# circuit_etudiant_2025.net
KiCad netlist of a schematic drawn in Altium Designer
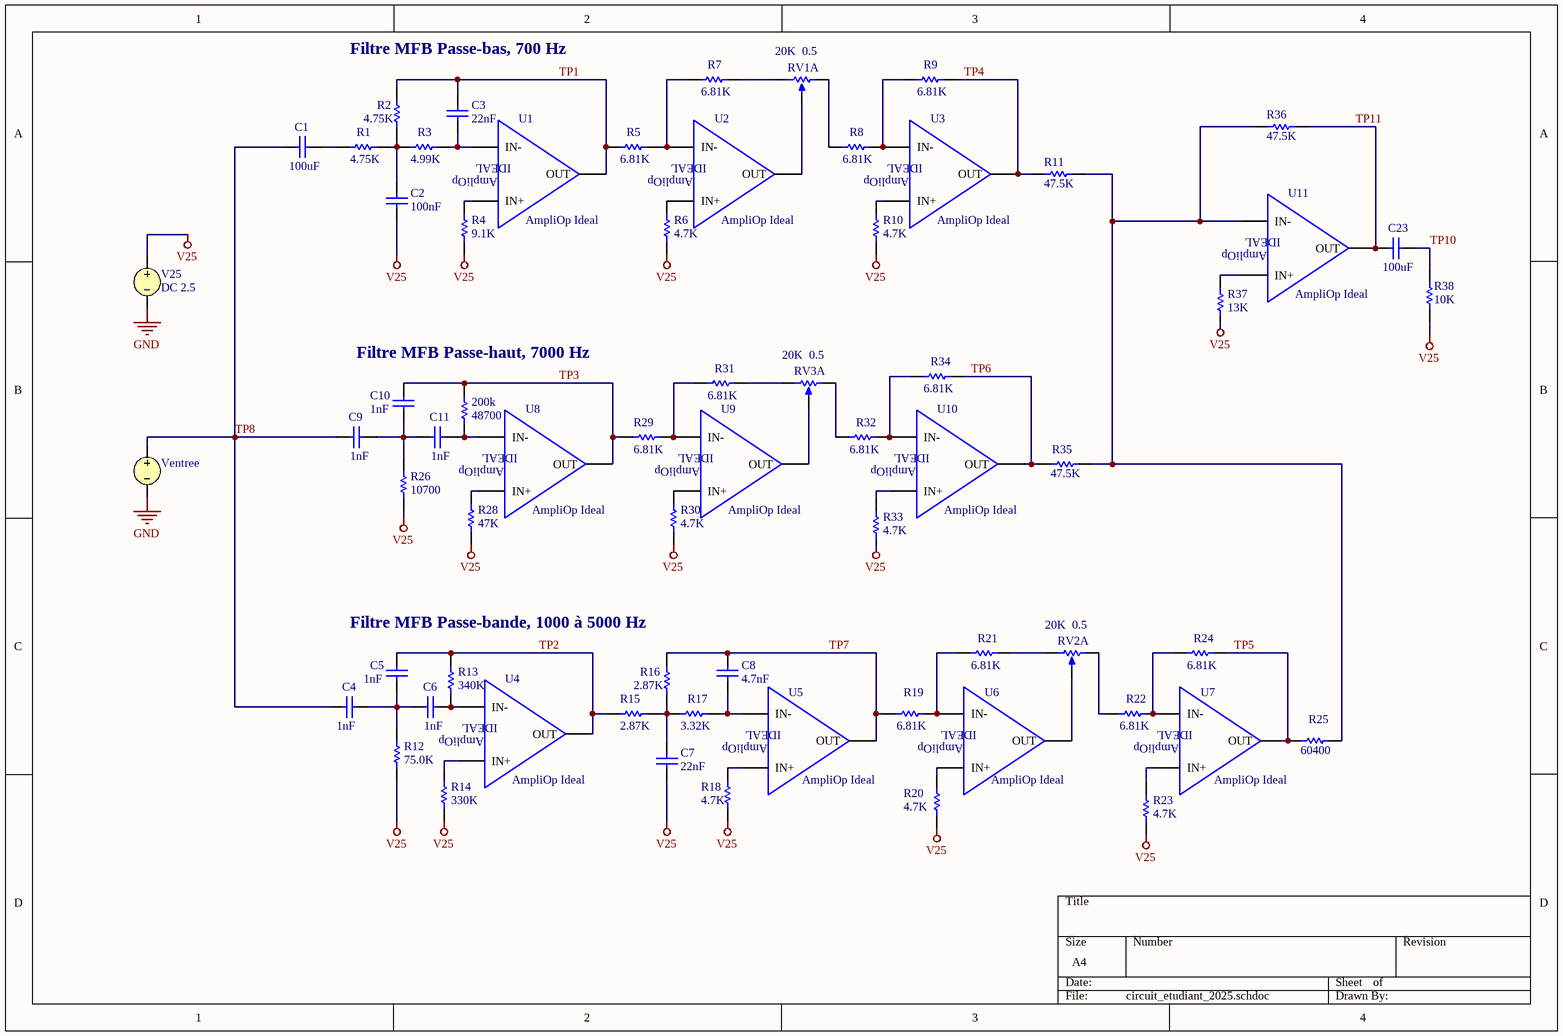
[diagram p0: circuit_etudiant_2025.schdoc]

(export (version "E")
  (design (tool "Eeschema 10.0.6"))
  (components
    (comp (ref "200k")
      (value "48700")
      (footprint "AXIAL-0.3")
      (description "Resistor")
      (fields (field (name "Comment") "Res1") (field (name "PUBLISHER") "Altium Limited"))
      (libsource (lib "Miscellaneous Devices") (part "Res1"))
    )
    (comp (ref "C1")
      (value "100uF")
      (footprint "RAD-0.3")
      (description "Capacitor")
      (fields (field (name "Comment") "Cap") (field (name "PUBLISHER") "Altium Limited"))
      (libsource (lib "Miscellaneous Devices") (part "Cap"))
    )
    (comp (ref "C2")
      (value "100nF")
      (footprint "RAD-0.3")
      (description "Capacitor")
      (fields (field (name "Comment") "Cap") (field (name "PUBLISHER") "Altium Limited"))
      (libsource (lib "Miscellaneous Devices") (part "Cap"))
    )
    (comp (ref "C3")
      (value "22nF")
      (footprint "RAD-0.3")
      (description "Capacitor")
      (fields (field (name "Comment") "Cap") (field (name "PUBLISHER") "Altium Limited"))
      (libsource (lib "Miscellaneous Devices") (part "Cap"))
    )
    (comp (ref "C4")
      (value "1nF")
      (footprint "RAD-0.3")
      (description "Capacitor")
      (fields (field (name "Comment") "Cap") (field (name "PUBLISHER") "Altium Limited"))
      (libsource (lib "Miscellaneous Devices") (part "Cap"))
    )
    (comp (ref "C5")
      (value "1nF")
      (footprint "RAD-0.3")
      (description "Capacitor")
      (fields (field (name "Comment") "Cap") (field (name "PUBLISHER") "Altium Limited"))
      (libsource (lib "Miscellaneous Devices") (part "Cap"))
    )
    (comp (ref "C6")
      (value "1nF")
      (footprint "RAD-0.3")
      (description "Capacitor")
      (fields (field (name "Comment") "Cap") (field (name "PUBLISHER") "Altium Limited"))
      (libsource (lib "Miscellaneous Devices") (part "Cap"))
    )
    (comp (ref "C7")
      (value "22nF")
      (footprint "RAD-0.3")
      (description "Capacitor")
      (fields (field (name "Comment") "Cap") (field (name "PUBLISHER") "Altium Limited"))
      (libsource (lib "Miscellaneous Devices") (part "Cap"))
    )
    (comp (ref "C8")
      (value "4.7nF")
      (footprint "RAD-0.3")
      (description "Capacitor")
      (fields (field (name "Comment") "Cap") (field (name "PUBLISHER") "Altium Limited"))
      (libsource (lib "Miscellaneous Devices") (part "Cap"))
    )
    (comp (ref "C9")
      (value "1nF")
      (footprint "RAD-0.3")
      (description "Capacitor")
      (fields (field (name "Comment") "Cap") (field (name "PUBLISHER") "Altium Limited"))
      (libsource (lib "Miscellaneous Devices") (part "Cap"))
    )
    (comp (ref "C10")
      (value "1nF")
      (footprint "RAD-0.3")
      (description "Capacitor")
      (fields (field (name "Comment") "Cap") (field (name "PUBLISHER") "Altium Limited"))
      (libsource (lib "Miscellaneous Devices") (part "Cap"))
    )
    (comp (ref "C11")
      (value "1nF")
      (footprint "RAD-0.3")
      (description "Capacitor")
      (fields (field (name "Comment") "Cap") (field (name "PUBLISHER") "Altium Limited"))
      (libsource (lib "Miscellaneous Devices") (part "Cap"))
    )
    (comp (ref "C23")
      (value "100uF")
      (footprint "RAD-0.3")
      (description "Capacitor")
      (fields (field (name "Comment") "Cap") (field (name "PUBLISHER") "Altium Limited"))
      (libsource (lib "Miscellaneous Devices") (part "Cap"))
    )
    (comp (ref "R1")
      (value "4.75K")
      (footprint "AXIAL-0.3")
      (description "Resistor")
      (fields (field (name "Comment") "Res1") (field (name "PUBLISHER") "Altium Limited"))
      (libsource (lib "Miscellaneous Devices") (part "Res1"))
    )
    (comp (ref "R2")
      (value "4.75K")
      (footprint "AXIAL-0.3")
      (description "Resistor")
      (fields (field (name "Comment") "Res1") (field (name "PUBLISHER") "Altium Limited"))
      (libsource (lib "Miscellaneous Devices") (part "Res1"))
    )
    (comp (ref "R3")
      (value "4.99K")
      (footprint "AXIAL-0.3")
      (description "Resistor")
      (fields (field (name "Comment") "Res1") (field (name "PUBLISHER") "Altium Limited"))
      (libsource (lib "Miscellaneous Devices") (part "Res1"))
    )
    (comp (ref "R4")
      (value "9.1K")
      (footprint "AXIAL-0.3")
      (description "Resistor")
      (fields (field (name "Comment") "Res1") (field (name "PUBLISHER") "Altium Limited"))
      (libsource (lib "Miscellaneous Devices") (part "Res1"))
    )
    (comp (ref "R5")
      (value "6.81K")
      (footprint "AXIAL-0.3")
      (description "Resistor")
      (fields (field (name "Comment") "Res1") (field (name "PUBLISHER") "Altium Limited"))
      (libsource (lib "Miscellaneous Devices") (part "Res1"))
    )
    (comp (ref "R6")
      (value "4.7K")
      (footprint "AXIAL-0.3")
      (description "Resistor")
      (fields (field (name "Comment") "Res1") (field (name "PUBLISHER") "Altium Limited"))
      (libsource (lib "Miscellaneous Devices") (part "Res1"))
    )
    (comp (ref "R7")
      (value "6.81K")
      (footprint "AXIAL-0.3")
      (description "Resistor")
      (fields (field (name "Comment") "Res1") (field (name "PUBLISHER") "Altium Limited"))
      (libsource (lib "Miscellaneous Devices") (part "Res1"))
    )
    (comp (ref "R8")
      (value "6.81K")
      (footprint "AXIAL-0.3")
      (description "Resistor")
      (fields (field (name "Comment") "Res1") (field (name "PUBLISHER") "Altium Limited"))
      (libsource (lib "Miscellaneous Devices") (part "Res1"))
    )
    (comp (ref "R9")
      (value "6.81K")
      (footprint "AXIAL-0.3")
      (description "Resistor")
      (fields (field (name "Comment") "Res1") (field (name "PUBLISHER") "Altium Limited"))
      (libsource (lib "Miscellaneous Devices") (part "Res1"))
    )
    (comp (ref "R10")
      (value "4.7K")
      (footprint "AXIAL-0.3")
      (description "Resistor")
      (fields (field (name "Comment") "Res1") (field (name "PUBLISHER") "Altium Limited"))
      (libsource (lib "Miscellaneous Devices") (part "Res1"))
    )
    (comp (ref "R11")
      (value "47.5K")
      (footprint "AXIAL-0.3")
      (description "Resistor")
      (fields (field (name "Comment") "Res1") (field (name "PUBLISHER") "Altium Limited"))
      (libsource (lib "Miscellaneous Devices") (part "Res1"))
    )
    (comp (ref "R12")
      (value "75.0K")
      (footprint "AXIAL-0.3")
      (description "Resistor")
      (fields (field (name "Comment") "Res1") (field (name "PUBLISHER") "Altium Limited"))
      (libsource (lib "Miscellaneous Devices") (part "Res1"))
    )
    (comp (ref "R13")
      (value "340K")
      (footprint "AXIAL-0.3")
      (description "Resistor")
      (fields (field (name "Comment") "Res1") (field (name "PUBLISHER") "Altium Limited"))
      (libsource (lib "Miscellaneous Devices") (part "Res1"))
    )
    (comp (ref "R14")
      (value "330K")
      (footprint "AXIAL-0.3")
      (description "Resistor")
      (fields (field (name "Comment") "Res1") (field (name "PUBLISHER") "Altium Limited"))
      (libsource (lib "Miscellaneous Devices") (part "Res1"))
    )
    (comp (ref "R15")
      (value "2.87K")
      (footprint "AXIAL-0.3")
      (description "Resistor")
      (fields (field (name "Comment") "Res1") (field (name "PUBLISHER") "Altium Limited"))
      (libsource (lib "Miscellaneous Devices") (part "Res1"))
    )
    (comp (ref "R16")
      (value "2.87K")
      (footprint "AXIAL-0.3")
      (description "Resistor")
      (fields (field (name "Comment") "Res1") (field (name "PUBLISHER") "Altium Limited"))
      (libsource (lib "Miscellaneous Devices") (part "Res1"))
    )
    (comp (ref "R17")
      (value "3.32K")
      (footprint "AXIAL-0.3")
      (description "Resistor")
      (fields (field (name "Comment") "Res1") (field (name "PUBLISHER") "Altium Limited"))
      (libsource (lib "Miscellaneous Devices") (part "Res1"))
    )
    (comp (ref "R18")
      (value "4.7K")
      (footprint "AXIAL-0.3")
      (description "Resistor")
      (fields (field (name "Comment") "Res1") (field (name "PUBLISHER") "Altium Limited"))
      (libsource (lib "Miscellaneous Devices") (part "Res1"))
    )
    (comp (ref "R19")
      (value "6.81K")
      (footprint "AXIAL-0.3")
      (description "Resistor")
      (fields (field (name "Comment") "Res1") (field (name "PUBLISHER") "Altium Limited"))
      (libsource (lib "Miscellaneous Devices") (part "Res1"))
    )
    (comp (ref "R20")
      (value "4.7K")
      (footprint "AXIAL-0.3")
      (description "Resistor")
      (fields (field (name "Comment") "Res1") (field (name "PUBLISHER") "Altium Limited"))
      (libsource (lib "Miscellaneous Devices") (part "Res1"))
    )
    (comp (ref "R21")
      (value "6.81K")
      (footprint "AXIAL-0.3")
      (description "Resistor")
      (fields (field (name "Comment") "Res1") (field (name "PUBLISHER") "Altium Limited"))
      (libsource (lib "Miscellaneous Devices") (part "Res1"))
    )
    (comp (ref "R22")
      (value "6.81K")
      (footprint "AXIAL-0.3")
      (description "Resistor")
      (fields (field (name "Comment") "Res1") (field (name "PUBLISHER") "Altium Limited"))
      (libsource (lib "Miscellaneous Devices") (part "Res1"))
    )
    (comp (ref "R23")
      (value "4.7K")
      (footprint "AXIAL-0.3")
      (description "Resistor")
      (fields (field (name "Comment") "Res1") (field (name "PUBLISHER") "Altium Limited"))
      (libsource (lib "Miscellaneous Devices") (part "Res1"))
    )
    (comp (ref "R24")
      (value "6.81K")
      (footprint "AXIAL-0.3")
      (description "Resistor")
      (fields (field (name "Comment") "Res1") (field (name "PUBLISHER") "Altium Limited"))
      (libsource (lib "Miscellaneous Devices") (part "Res1"))
    )
    (comp (ref "R25")
      (value "60400")
      (footprint "AXIAL-0.3")
      (description "Resistor")
      (fields (field (name "Comment") "Res1") (field (name "PUBLISHER") "Altium Limited"))
      (libsource (lib "Miscellaneous Devices") (part "Res1"))
    )
    (comp (ref "R26")
      (value "10700")
      (footprint "AXIAL-0.3")
      (description "Resistor")
      (fields (field (name "Comment") "Res1") (field (name "PUBLISHER") "Altium Limited"))
      (libsource (lib "Miscellaneous Devices") (part "Res1"))
    )
    (comp (ref "R28")
      (value "47K")
      (footprint "AXIAL-0.3")
      (description "Resistor")
      (fields (field (name "Comment") "Res1") (field (name "PUBLISHER") "Altium Limited"))
      (libsource (lib "Miscellaneous Devices") (part "Res1"))
    )
    (comp (ref "R29")
      (value "6.81K")
      (footprint "AXIAL-0.3")
      (description "Resistor")
      (fields (field (name "Comment") "Res1") (field (name "PUBLISHER") "Altium Limited"))
      (libsource (lib "Miscellaneous Devices") (part "Res1"))
    )
    (comp (ref "R30")
      (value "4.7K")
      (footprint "AXIAL-0.3")
      (description "Resistor")
      (fields (field (name "Comment") "Res1") (field (name "PUBLISHER") "Altium Limited"))
      (libsource (lib "Miscellaneous Devices") (part "Res1"))
    )
    (comp (ref "R31")
      (value "6.81K")
      (footprint "AXIAL-0.3")
      (description "Resistor")
      (fields (field (name "Comment") "Res1") (field (name "PUBLISHER") "Altium Limited"))
      (libsource (lib "Miscellaneous Devices") (part "Res1"))
    )
    (comp (ref "R32")
      (value "6.81K")
      (footprint "AXIAL-0.3")
      (description "Resistor")
      (fields (field (name "Comment") "Res1") (field (name "PUBLISHER") "Altium Limited"))
      (libsource (lib "Miscellaneous Devices") (part "Res1"))
    )
    (comp (ref "R33")
      (value "4.7K")
      (footprint "AXIAL-0.3")
      (description "Resistor")
      (fields (field (name "Comment") "Res1") (field (name "PUBLISHER") "Altium Limited"))
      (libsource (lib "Miscellaneous Devices") (part "Res1"))
    )
    (comp (ref "R34")
      (value "6.81K")
      (footprint "AXIAL-0.3")
      (description "Resistor")
      (fields (field (name "Comment") "Res1") (field (name "PUBLISHER") "Altium Limited"))
      (libsource (lib "Miscellaneous Devices") (part "Res1"))
    )
    (comp (ref "R35")
      (value "47.5K")
      (footprint "AXIAL-0.3")
      (description "Resistor")
      (fields (field (name "Comment") "Res1") (field (name "PUBLISHER") "Altium Limited"))
      (libsource (lib "Miscellaneous Devices") (part "Res1"))
    )
    (comp (ref "R36")
      (value "47.5K")
      (footprint "AXIAL-0.3")
      (description "Resistor")
      (fields (field (name "Comment") "Res1") (field (name "PUBLISHER") "Altium Limited"))
      (libsource (lib "Miscellaneous Devices") (part "Res1"))
    )
    (comp (ref "R37")
      (value "13K")
      (footprint "AXIAL-0.3")
      (description "Resistor")
      (fields (field (name "Comment") "Res1") (field (name "PUBLISHER") "Altium Limited"))
      (libsource (lib "Miscellaneous Devices") (part "Res1"))
    )
    (comp (ref "R38")
      (value "10K")
      (footprint "AXIAL-0.3")
      (description "Resistor")
      (fields (field (name "Comment") "Res1") (field (name "PUBLISHER") "Altium Limited"))
      (libsource (lib "Miscellaneous Devices") (part "Res1"))
    )
    (comp (ref "RV1A")
      (value "20K")
      (footprint "VR5")
      (description "Potentiometer")
      (fields
        (field (name "SET POSITION") "0.5")
        (field (name "Comment") "RPot")
        (field (name "PUBLISHER") "Altium Limited")
      )
      (libsource (lib "Miscellaneous Devices") (part "RPot"))
    )
    (comp (ref "RV2A")
      (value "20K")
      (footprint "VR5")
      (description "Potentiometer")
      (fields
        (field (name "SET POSITION") "0.5")
        (field (name "Comment") "RPot")
        (field (name "PUBLISHER") "Altium Limited")
      )
      (libsource (lib "Miscellaneous Devices") (part "RPot"))
    )
    (comp (ref "RV3A")
      (value "20K")
      (footprint "VR5")
      (description "Potentiometer")
      (fields
        (field (name "SET POSITION") "0.5")
        (field (name "Comment") "RPot")
        (field (name "PUBLISHER") "Altium Limited")
      )
      (libsource (lib "Miscellaneous Devices") (part "RPot"))
    )
    (comp (ref "U1") (value "AmpliOp Ideal") (libsource (lib "Librarie_S2") (part "AmpliOp_ideal")))
    (comp (ref "U2") (value "AmpliOp Ideal") (libsource (lib "Librarie_S2") (part "AmpliOp_ideal")))
    (comp (ref "U3") (value "AmpliOp Ideal") (libsource (lib "Librarie_S2") (part "AmpliOp_ideal")))
    (comp (ref "U4") (value "AmpliOp Ideal") (libsource (lib "Librarie_S2") (part "AmpliOp_ideal")))
    (comp (ref "U5") (value "AmpliOp Ideal") (libsource (lib "Librarie_S2") (part "AmpliOp_ideal")))
    (comp (ref "U6") (value "AmpliOp Ideal") (libsource (lib "Librarie_S2") (part "AmpliOp_ideal")))
    (comp (ref "U7") (value "AmpliOp Ideal") (libsource (lib "Librarie_S2") (part "AmpliOp_ideal")))
    (comp (ref "U8") (value "AmpliOp Ideal") (libsource (lib "Librarie_S2") (part "AmpliOp_ideal")))
    (comp (ref "U9") (value "AmpliOp Ideal") (libsource (lib "Librarie_S2") (part "AmpliOp_ideal")))
    (comp (ref "U10") (value "AmpliOp Ideal") (libsource (lib "Librarie_S2") (part "AmpliOp_ideal")))
    (comp (ref "U11") (value "AmpliOp Ideal") (libsource (lib "Librarie_S2") (part "AmpliOp_ideal")))
    (comp (ref "V25")
      (value "DC 2.5")
      (description "Voltage Source")
      (fields (field (name "PUBLISHER") "Altium Limited"))
      (libsource (lib "Simulation Generic Components") (part "VSRC"))
    )
    (comp (ref "Ventree")
      (value "PULSE(0 1 100n 10n 10n 400n 1u 0)")
      (description "Voltage Source")
      (fields (field (name "PUBLISHER") "Altium Limited"))
      (libsource (lib "Simulation Generic Components") (part "VSRC"))
    )
  )
  (nets
    (net (code "1") (name "/TP1") (class "Default")
      (node (ref "C3") (pin "1") (pinfunction "1_1") (pintype "passive"))
      (node (ref "R2") (pin "1") (pinfunction "1_1") (pintype "passive"))
      (node (ref "R5") (pin "1") (pinfunction "1_1") (pintype "passive"))
      (node (ref "U1") (pin "3") (pinfunction "OUT_3") (pintype "passive"))
    )
    (net (code "2") (name "/TP2") (class "Default")
      (node (ref "C5") (pin "1") (pinfunction "1_1") (pintype "passive"))
      (node (ref "R13") (pin "1") (pinfunction "1_1") (pintype "passive"))
      (node (ref "R15") (pin "1") (pinfunction "1_1") (pintype "passive"))
      (node (ref "U4") (pin "3") (pinfunction "OUT_3") (pintype "passive"))
    )
    (net (code "3") (name "/TP3") (class "Default")
      (node (ref "200k") (pin "1") (pinfunction "1_1") (pintype "passive"))
      (node (ref "C10") (pin "1") (pinfunction "1_1") (pintype "passive"))
      (node (ref "R29") (pin "1") (pinfunction "1_1") (pintype "passive"))
      (node (ref "U8") (pin "3") (pinfunction "OUT_3") (pintype "passive"))
    )
    (net (code "4") (name "/TP4") (class "Default")
      (node (ref "R11") (pin "1") (pinfunction "1_1") (pintype "passive"))
      (node (ref "R9") (pin "2") (pinfunction "2_2") (pintype "passive"))
      (node (ref "U3") (pin "3") (pinfunction "OUT_3") (pintype "passive"))
    )
    (net (code "5") (name "/TP5") (class "Default")
      (node (ref "R24") (pin "2") (pinfunction "2_2") (pintype "passive"))
      (node (ref "R25") (pin "1") (pinfunction "1_1") (pintype "passive"))
      (node (ref "U7") (pin "3") (pinfunction "OUT_3") (pintype "passive"))
    )
    (net (code "6") (name "/TP6") (class "Default")
      (node (ref "R34") (pin "2") (pinfunction "2_2") (pintype "passive"))
      (node (ref "R35") (pin "1") (pinfunction "1_1") (pintype "passive"))
      (node (ref "U10") (pin "3") (pinfunction "OUT_3") (pintype "passive"))
    )
    (net (code "7") (name "/TP7") (class "Default")
      (node (ref "C8") (pin "1") (pinfunction "1_1") (pintype "passive"))
      (node (ref "R16") (pin "1") (pinfunction "1_1") (pintype "passive"))
      (node (ref "R19") (pin "1") (pinfunction "1_1") (pintype "passive"))
      (node (ref "U5") (pin "3") (pinfunction "OUT_3") (pintype "passive"))
    )
    (net (code "8") (name "/TP8") (class "Default")
      (node (ref "C1") (pin "1") (pinfunction "1_1") (pintype "passive"))
      (node (ref "C4") (pin "1") (pinfunction "1_1") (pintype "passive"))
      (node (ref "C9") (pin "1") (pinfunction "1_1") (pintype "passive"))
      (node (ref "Ventree") (pin "1") (pinfunction "1_1") (pintype "passive"))
    )
    (net (code "9") (name "/TP10") (class "Default")
      (node (ref "C23") (pin "2") (pinfunction "2_2") (pintype "passive"))
      (node (ref "R38") (pin "2") (pinfunction "2_2") (pintype "passive"))
    )
    (net (code "10") (name "/TP11") (class "Default")
      (node (ref "C23") (pin "1") (pinfunction "1_1") (pintype "passive"))
      (node (ref "R36") (pin "2") (pinfunction "2_2") (pintype "passive"))
      (node (ref "U11") (pin "3") (pinfunction "OUT_3") (pintype "passive"))
    )
    (net (code "11") (name "GND") (class "Default")
      (node (ref "V25") (pin "2") (pinfunction "2_2") (pintype "passive"))
      (node (ref "Ventree") (pin "2") (pinfunction "2_2") (pintype "passive"))
    )
    (net (code "12") (name "Net-(C1-Pad2)") (class "Default")
      (node (ref "C1") (pin "2") (pinfunction "2_2") (pintype "passive"))
      (node (ref "R1") (pin "1") (pinfunction "1_1") (pintype "passive"))
    )
    (net (code "13") (name "Net-(C2-Pad1)") (class "Default")
      (node (ref "C2") (pin "1") (pinfunction "1_1") (pintype "passive"))
      (node (ref "R1") (pin "2") (pinfunction "2_2") (pintype "passive"))
      (node (ref "R2") (pin "2") (pinfunction "2_2") (pintype "passive"))
      (node (ref "R3") (pin "1") (pinfunction "1_1") (pintype "passive"))
    )
    (net (code "14") (name "Net-(C4-Pad2)") (class "Default")
      (node (ref "C4") (pin "2") (pinfunction "2_2") (pintype "passive"))
      (node (ref "C5") (pin "2") (pinfunction "2_2") (pintype "passive"))
      (node (ref "C6") (pin "1") (pinfunction "1_1") (pintype "passive"))
      (node (ref "R12") (pin "1") (pinfunction "1_1") (pintype "passive"))
    )
    (net (code "15") (name "Net-(C7-Pad1)") (class "Default")
      (node (ref "C7") (pin "1") (pinfunction "1_1") (pintype "passive"))
      (node (ref "R15") (pin "2") (pinfunction "2_2") (pintype "passive"))
      (node (ref "R16") (pin "2") (pinfunction "2_2") (pintype "passive"))
      (node (ref "R17") (pin "1") (pinfunction "1_1") (pintype "passive"))
    )
    (net (code "16") (name "Net-(C10-Pad2)") (class "Default")
      (node (ref "C10") (pin "2") (pinfunction "2_2") (pintype "passive"))
      (node (ref "C11") (pin "1") (pinfunction "1_1") (pintype "passive"))
      (node (ref "C9") (pin "2") (pinfunction "2_2") (pintype "passive"))
      (node (ref "R26") (pin "1") (pinfunction "1_1") (pintype "passive"))
    )
    (net (code "17") (name "Net-(RV1A-BOT)") (class "Default")
      (node (ref "R8") (pin "1") (pinfunction "1_1") (pintype "passive"))
      (node (ref "RV1A") (pin "2") (pinfunction "BOT_2") (pintype "passive"))
    )
    (net (code "18") (name "Net-(RV1A-TAP)") (class "Default")
      (node (ref "RV1A") (pin "3") (pinfunction "TAP_3") (pintype "passive"))
      (node (ref "U2") (pin "3") (pinfunction "OUT_3") (pintype "passive"))
    )
    (net (code "19") (name "Net-(RV1A-TOP)") (class "Default")
      (node (ref "R7") (pin "2") (pinfunction "2_2") (pintype "passive"))
      (node (ref "RV1A") (pin "1") (pinfunction "TOP_1") (pintype "passive"))
    )
    (net (code "20") (name "Net-(RV2A-BOT)") (class "Default")
      (node (ref "R22") (pin "1") (pinfunction "1_1") (pintype "passive"))
      (node (ref "RV2A") (pin "2") (pinfunction "BOT_2") (pintype "passive"))
    )
    (net (code "21") (name "Net-(RV2A-TAP)") (class "Default")
      (node (ref "RV2A") (pin "3") (pinfunction "TAP_3") (pintype "passive"))
      (node (ref "U6") (pin "3") (pinfunction "OUT_3") (pintype "passive"))
    )
    (net (code "22") (name "Net-(RV2A-TOP)") (class "Default")
      (node (ref "R21") (pin "2") (pinfunction "2_2") (pintype "passive"))
      (node (ref "RV2A") (pin "1") (pinfunction "TOP_1") (pintype "passive"))
    )
    (net (code "23") (name "Net-(RV3A-BOT)") (class "Default")
      (node (ref "R32") (pin "1") (pinfunction "1_1") (pintype "passive"))
      (node (ref "RV3A") (pin "2") (pinfunction "BOT_2") (pintype "passive"))
    )
    (net (code "24") (name "Net-(RV3A-TAP)") (class "Default")
      (node (ref "RV3A") (pin "3") (pinfunction "TAP_3") (pintype "passive"))
      (node (ref "U9") (pin "3") (pinfunction "OUT_3") (pintype "passive"))
    )
    (net (code "25") (name "Net-(RV3A-TOP)") (class "Default")
      (node (ref "R31") (pin "2") (pinfunction "2_2") (pintype "passive"))
      (node (ref "RV3A") (pin "1") (pinfunction "TOP_1") (pintype "passive"))
    )
    (net (code "26") (name "Net-(U1-IN+)") (class "Default")
      (node (ref "R4") (pin "1") (pinfunction "1_1") (pintype "passive"))
      (node (ref "U1") (pin "1") (pinfunction "IN+_1") (pintype "passive"))
    )
    (net (code "27") (name "Net-(U1-IN-)") (class "Default")
      (node (ref "C3") (pin "2") (pinfunction "2_2") (pintype "passive"))
      (node (ref "R3") (pin "2") (pinfunction "2_2") (pintype "passive"))
      (node (ref "U1") (pin "2") (pinfunction "IN-_2") (pintype "passive"))
    )
    (net (code "28") (name "Net-(U2-IN+)") (class "Default")
      (node (ref "R6") (pin "1") (pinfunction "1_1") (pintype "passive"))
      (node (ref "U2") (pin "1") (pinfunction "IN+_1") (pintype "passive"))
    )
    (net (code "29") (name "Net-(U2-IN-)") (class "Default")
      (node (ref "R5") (pin "2") (pinfunction "2_2") (pintype "passive"))
      (node (ref "R7") (pin "1") (pinfunction "1_1") (pintype "passive"))
      (node (ref "U2") (pin "2") (pinfunction "IN-_2") (pintype "passive"))
    )
    (net (code "30") (name "Net-(U3-IN+)") (class "Default")
      (node (ref "R10") (pin "1") (pinfunction "1_1") (pintype "passive"))
      (node (ref "U3") (pin "1") (pinfunction "IN+_1") (pintype "passive"))
    )
    (net (code "31") (name "Net-(U3-IN-)") (class "Default")
      (node (ref "R8") (pin "2") (pinfunction "2_2") (pintype "passive"))
      (node (ref "R9") (pin "1") (pinfunction "1_1") (pintype "passive"))
      (node (ref "U3") (pin "2") (pinfunction "IN-_2") (pintype "passive"))
    )
    (net (code "32") (name "Net-(U4-IN+)") (class "Default")
      (node (ref "R14") (pin "1") (pinfunction "1_1") (pintype "passive"))
      (node (ref "U4") (pin "1") (pinfunction "IN+_1") (pintype "passive"))
    )
    (net (code "33") (name "Net-(U4-IN-)") (class "Default")
      (node (ref "C6") (pin "2") (pinfunction "2_2") (pintype "passive"))
      (node (ref "R13") (pin "2") (pinfunction "2_2") (pintype "passive"))
      (node (ref "U4") (pin "2") (pinfunction "IN-_2") (pintype "passive"))
    )
    (net (code "34") (name "Net-(U5-IN+)") (class "Default")
      (node (ref "R18") (pin "1") (pinfunction "1_1") (pintype "passive"))
      (node (ref "U5") (pin "1") (pinfunction "IN+_1") (pintype "passive"))
    )
    (net (code "35") (name "Net-(U5-IN-)") (class "Default")
      (node (ref "C8") (pin "2") (pinfunction "2_2") (pintype "passive"))
      (node (ref "R17") (pin "2") (pinfunction "2_2") (pintype "passive"))
      (node (ref "U5") (pin "2") (pinfunction "IN-_2") (pintype "passive"))
    )
    (net (code "36") (name "Net-(U6-IN+)") (class "Default")
      (node (ref "R20") (pin "1") (pinfunction "1_1") (pintype "passive"))
      (node (ref "U6") (pin "1") (pinfunction "IN+_1") (pintype "passive"))
    )
    (net (code "37") (name "Net-(U6-IN-)") (class "Default")
      (node (ref "R19") (pin "2") (pinfunction "2_2") (pintype "passive"))
      (node (ref "R21") (pin "1") (pinfunction "1_1") (pintype "passive"))
      (node (ref "U6") (pin "2") (pinfunction "IN-_2") (pintype "passive"))
    )
    (net (code "38") (name "Net-(U7-IN+)") (class "Default")
      (node (ref "R23") (pin "1") (pinfunction "1_1") (pintype "passive"))
      (node (ref "U7") (pin "1") (pinfunction "IN+_1") (pintype "passive"))
    )
    (net (code "39") (name "Net-(U7-IN-)") (class "Default")
      (node (ref "R22") (pin "2") (pinfunction "2_2") (pintype "passive"))
      (node (ref "R24") (pin "1") (pinfunction "1_1") (pintype "passive"))
      (node (ref "U7") (pin "2") (pinfunction "IN-_2") (pintype "passive"))
    )
    (net (code "40") (name "Net-(U8-IN+)") (class "Default")
      (node (ref "R28") (pin "1") (pinfunction "1_1") (pintype "passive"))
      (node (ref "U8") (pin "1") (pinfunction "IN+_1") (pintype "passive"))
    )
    (net (code "41") (name "Net-(U8-IN-)") (class "Default")
      (node (ref "200k") (pin "2") (pinfunction "2_2") (pintype "passive"))
      (node (ref "C11") (pin "2") (pinfunction "2_2") (pintype "passive"))
      (node (ref "U8") (pin "2") (pinfunction "IN-_2") (pintype "passive"))
    )
    (net (code "42") (name "Net-(U9-IN+)") (class "Default")
      (node (ref "R30") (pin "1") (pinfunction "1_1") (pintype "passive"))
      (node (ref "U9") (pin "1") (pinfunction "IN+_1") (pintype "passive"))
    )
    (net (code "43") (name "Net-(U9-IN-)") (class "Default")
      (node (ref "R29") (pin "2") (pinfunction "2_2") (pintype "passive"))
      (node (ref "R31") (pin "1") (pinfunction "1_1") (pintype "passive"))
      (node (ref "U9") (pin "2") (pinfunction "IN-_2") (pintype "passive"))
    )
    (net (code "44") (name "Net-(U10-IN+)") (class "Default")
      (node (ref "R33") (pin "1") (pinfunction "1_1") (pintype "passive"))
      (node (ref "U10") (pin "1") (pinfunction "IN+_1") (pintype "passive"))
    )
    (net (code "45") (name "Net-(U10-IN-)") (class "Default")
      (node (ref "R32") (pin "2") (pinfunction "2_2") (pintype "passive"))
      (node (ref "R34") (pin "1") (pinfunction "1_1") (pintype "passive"))
      (node (ref "U10") (pin "2") (pinfunction "IN-_2") (pintype "passive"))
    )
    (net (code "46") (name "Net-(U11-IN+)") (class "Default")
      (node (ref "R37") (pin "1") (pinfunction "1_1") (pintype "passive"))
      (node (ref "U11") (pin "1") (pinfunction "IN+_1") (pintype "passive"))
    )
    (net (code "47") (name "Net-(U11-IN-)") (class "Default")
      (node (ref "R11") (pin "2") (pinfunction "2_2") (pintype "passive"))
      (node (ref "R25") (pin "2") (pinfunction "2_2") (pintype "passive"))
      (node (ref "R35") (pin "2") (pinfunction "2_2") (pintype "passive"))
      (node (ref "R36") (pin "1") (pinfunction "1_1") (pintype "passive"))
      (node (ref "U11") (pin "2") (pinfunction "IN-_2") (pintype "passive"))
    )
    (net (code "48") (name "V25") (class "Default")
      (node (ref "C2") (pin "2") (pinfunction "2_2") (pintype "passive"))
      (node (ref "C7") (pin "2") (pinfunction "2_2") (pintype "passive"))
      (node (ref "R10") (pin "2") (pinfunction "2_2") (pintype "passive"))
      (node (ref "R12") (pin "2") (pinfunction "2_2") (pintype "passive"))
      (node (ref "R14") (pin "2") (pinfunction "2_2") (pintype "passive"))
      (node (ref "R18") (pin "2") (pinfunction "2_2") (pintype "passive"))
      (node (ref "R20") (pin "2") (pinfunction "2_2") (pintype "passive"))
      (node (ref "R23") (pin "2") (pinfunction "2_2") (pintype "passive"))
      (node (ref "R26") (pin "2") (pinfunction "2_2") (pintype "passive"))
      (node (ref "R28") (pin "2") (pinfunction "2_2") (pintype "passive"))
      (node (ref "R30") (pin "2") (pinfunction "2_2") (pintype "passive"))
      (node (ref "R33") (pin "2") (pinfunction "2_2") (pintype "passive"))
      (node (ref "R37") (pin "2") (pinfunction "2_2") (pintype "passive"))
      (node (ref "R38") (pin "1") (pinfunction "1_1") (pintype "passive"))
      (node (ref "R4") (pin "2") (pinfunction "2_2") (pintype "passive"))
      (node (ref "R6") (pin "2") (pinfunction "2_2") (pintype "passive"))
      (node (ref "V25") (pin "1") (pinfunction "1_1") (pintype "passive"))
    )
  )
)
